# Supply.net
KiCad netlist of a schematic drawn in Altium Designer
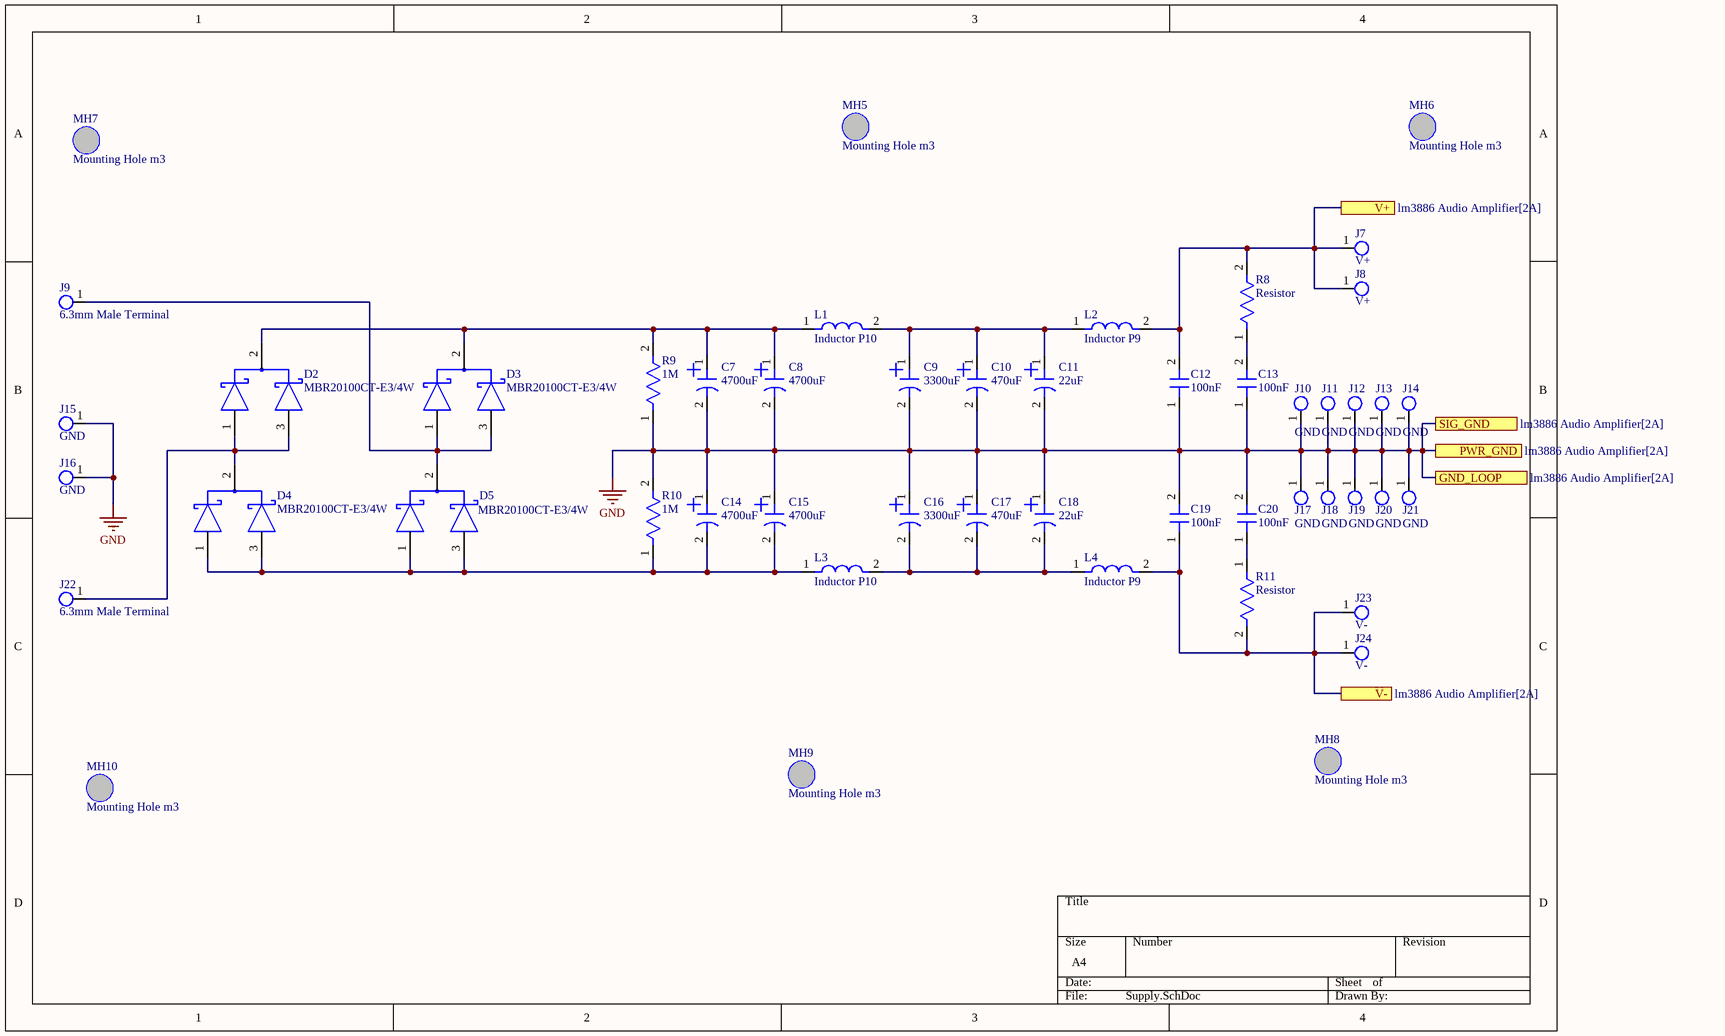
[diagram p0: Supply.SchDoc]

(export (version "E")
  (design (tool "Eeschema 10.0.6"))
  (components
    (comp (ref "C7")
      (value "4700uF")
      (footprint "Capacitor electrolytic 25x41mm")
      (libsource (lib "lm3886 Schlib") (part "Capacitor Polar"))
    )
    (comp (ref "C8")
      (value "4700uF")
      (footprint "Capacitor electrolytic 25x41mm")
      (libsource (lib "lm3886 Schlib") (part "Capacitor Polar"))
    )
    (comp (ref "C9")
      (value "3300uF")
      (footprint "Capacitor electrolytic 16x21mm")
      (libsource (lib "lm3886 Schlib") (part "Capacitor Polar"))
    )
    (comp (ref "C10")
      (value "470uF")
      (footprint "Capacitor electrolytic 10x16mm")
      (libsource (lib "lm3886 Schlib") (part "Capacitor Polar"))
    )
    (comp (ref "C11")
      (value "22uF")
      (footprint "Capacitor electrolytic 5x11mm")
      (libsource (lib "lm3886 Schlib") (part "Capacitor Polar"))
    )
    (comp (ref "C12")
      (value "100nF")
      (footprint "Capacitor P5 3x7.5mm")
      (libsource (lib "lm3886 Schlib") (part "Capacitor"))
    )
    (comp (ref "C13")
      (value "100nF")
      (footprint "Capacitor P5 5x7.5mm")
      (libsource (lib "lm3886 Schlib") (part "Capacitor"))
    )
    (comp (ref "C14")
      (value "4700uF")
      (footprint "Capacitor electrolytic 25x41mm")
      (libsource (lib "lm3886 Schlib") (part "Capacitor Polar"))
    )
    (comp (ref "C15")
      (value "4700uF")
      (footprint "Capacitor electrolytic 25x41mm")
      (libsource (lib "lm3886 Schlib") (part "Capacitor Polar"))
    )
    (comp (ref "C16")
      (value "3300uF")
      (footprint "Capacitor electrolytic 16x21mm")
      (libsource (lib "lm3886 Schlib") (part "Capacitor Polar"))
    )
    (comp (ref "C17")
      (value "470uF")
      (footprint "Capacitor electrolytic 10x16mm")
      (libsource (lib "lm3886 Schlib") (part "Capacitor Polar"))
    )
    (comp (ref "C18")
      (value "22uF")
      (footprint "Capacitor electrolytic 5x11mm")
      (libsource (lib "lm3886 Schlib") (part "Capacitor Polar"))
    )
    (comp (ref "C19")
      (value "100nF")
      (footprint "Capacitor P5 3x7.5mm")
      (libsource (lib "lm3886 Schlib") (part "Capacitor"))
    )
    (comp (ref "C20")
      (value "100nF")
      (footprint "Capacitor P5 5x7.5mm")
      (libsource (lib "lm3886 Schlib") (part "Capacitor"))
    )
    (comp (ref "D2")
      (value "MBR20100CT-E3/4W")
      (footprint "FP-MBR20100CT-E3-4W-MFG")
      (description "MBR20100CT-E3/4W Dual Common-Cathode High-Voltage Schottky Rectifier")
      (libsource (lib "Altium Content Vault") (part "213139fa27cf652ab25f6c90a0a0ee5"))
    )
    (comp (ref "D3")
      (value "MBR20100CT-E3/4W")
      (footprint "FP-MBR20100CT-E3-4W-MFG")
      (description "MBR20100CT-E3/4W Dual Common-Cathode High-Voltage Schottky Rectifier")
      (libsource (lib "Altium Content Vault") (part "213139fa27cf652ab25f6c90a0a0ee5"))
    )
    (comp (ref "D4")
      (value "MBR20100CT-E3/4W")
      (footprint "FP-MBR20100CT-E3-4W-MFG")
      (description "MBR20100CT-E3/4W Dual Common-Cathode High-Voltage Schottky Rectifier")
      (libsource (lib "Altium Content Vault") (part "213139fa27cf652ab25f6c90a0a0ee5"))
    )
    (comp (ref "D5")
      (value "MBR20100CT-E3/4W")
      (footprint "FP-MBR20100CT-E3-4W-MFG")
      (description "MBR20100CT-E3/4W Dual Common-Cathode High-Voltage Schottky Rectifier")
      (libsource (lib "Altium Content Vault") (part "213139fa27cf652ab25f6c90a0a0ee5"))
    )
    (comp (ref "J7")
      (value "V+")
      (footprint "Terminal 6.3mm male")
      (libsource (lib "lm3886 Schlib") (part "6.3mm Male Terminal"))
    )
    (comp (ref "J8")
      (value "V+")
      (footprint "Terminal 6.3mm male")
      (libsource (lib "lm3886 Schlib") (part "6.3mm Male Terminal"))
    )
    (comp (ref "J9")
      (value "6.3mm Male Terminal")
      (footprint "Terminal 6.3mm male")
      (libsource (lib "lm3886 Schlib") (part "6.3mm Male Terminal"))
    )
    (comp (ref "J10")
      (value "GND")
      (footprint "Terminal 6.3mm male")
      (libsource (lib "lm3886 Schlib") (part "6.3mm Male Terminal"))
    )
    (comp (ref "J11")
      (value "GND")
      (footprint "Terminal 6.3mm male")
      (libsource (lib "lm3886 Schlib") (part "6.3mm Male Terminal"))
    )
    (comp (ref "J12")
      (value "GND")
      (footprint "Terminal 6.3mm male")
      (libsource (lib "lm3886 Schlib") (part "6.3mm Male Terminal"))
    )
    (comp (ref "J13")
      (value "GND")
      (footprint "Terminal 6.3mm male")
      (libsource (lib "lm3886 Schlib") (part "6.3mm Male Terminal"))
    )
    (comp (ref "J14")
      (value "GND")
      (footprint "Terminal 6.3mm male")
      (libsource (lib "lm3886 Schlib") (part "6.3mm Male Terminal"))
    )
    (comp (ref "J15")
      (value "GND")
      (footprint "Terminal 6.3mm male")
      (libsource (lib "lm3886 Schlib") (part "6.3mm Male Terminal"))
    )
    (comp (ref "J16")
      (value "GND")
      (footprint "Terminal 6.3mm male")
      (libsource (lib "lm3886 Schlib") (part "6.3mm Male Terminal"))
    )
    (comp (ref "J17")
      (value "GND")
      (footprint "Terminal 6.3mm male")
      (libsource (lib "lm3886 Schlib") (part "6.3mm Male Terminal"))
    )
    (comp (ref "J18")
      (value "GND")
      (footprint "Terminal 6.3mm male")
      (libsource (lib "lm3886 Schlib") (part "6.3mm Male Terminal"))
    )
    (comp (ref "J19")
      (value "GND")
      (footprint "Terminal 6.3mm male")
      (libsource (lib "lm3886 Schlib") (part "6.3mm Male Terminal"))
    )
    (comp (ref "J20")
      (value "GND")
      (footprint "Terminal 6.3mm male")
      (libsource (lib "lm3886 Schlib") (part "6.3mm Male Terminal"))
    )
    (comp (ref "J21")
      (value "GND")
      (footprint "Terminal 6.3mm male")
      (libsource (lib "lm3886 Schlib") (part "6.3mm Male Terminal"))
    )
    (comp (ref "J22")
      (value "6.3mm Male Terminal")
      (footprint "Terminal 6.3mm male")
      (libsource (lib "lm3886 Schlib") (part "6.3mm Male Terminal"))
    )
    (comp (ref "J23")
      (value "V-")
      (footprint "Terminal 6.3mm male")
      (libsource (lib "lm3886 Schlib") (part "6.3mm Male Terminal"))
    )
    (comp (ref "J24")
      (value "V-")
      (footprint "Terminal 6.3mm male")
      (libsource (lib "lm3886 Schlib") (part "6.3mm Male Terminal"))
    )
    (comp (ref "L1")
      (value "Inductor P10")
      (footprint "Inductor p10")
      (libsource (lib "lm3886 Schlib") (part "Inductor"))
    )
    (comp (ref "L2")
      (value "Inductor P9")
      (footprint "Inductor p10")
      (libsource (lib "lm3886 Schlib") (part "Inductor"))
    )
    (comp (ref "L3")
      (value "Inductor P10")
      (footprint "Inductor p10")
      (libsource (lib "lm3886 Schlib") (part "Inductor"))
    )
    (comp (ref "L4")
      (value "Inductor P9")
      (footprint "Inductor p10")
      (libsource (lib "lm3886 Schlib") (part "Inductor"))
    )
    (comp (ref "MH5")
      (value "Mounting Hole m3")
      (footprint "Mounting Hole")
      (libsource (lib "lm3886 Schlib") (part "Mounting Hole m3"))
    )
    (comp (ref "MH6")
      (value "Mounting Hole m3")
      (footprint "Mounting Hole")
      (libsource (lib "lm3886 Schlib") (part "Mounting Hole m3"))
    )
    (comp (ref "MH7")
      (value "Mounting Hole m3")
      (footprint "Mounting Hole")
      (libsource (lib "lm3886 Schlib") (part "Mounting Hole m3"))
    )
    (comp (ref "MH8")
      (value "Mounting Hole m3")
      (footprint "Mounting Hole")
      (libsource (lib "lm3886 Schlib") (part "Mounting Hole m3"))
    )
    (comp (ref "MH9")
      (value "Mounting Hole m3")
      (footprint "Mounting Hole")
      (libsource (lib "lm3886 Schlib") (part "Mounting Hole m3"))
    )
    (comp (ref "MH10")
      (value "Mounting Hole m3")
      (footprint "Mounting Hole")
      (libsource (lib "lm3886 Schlib") (part "Mounting Hole m3"))
    )
    (comp (ref "R8")
      (value "Resistor")
      (footprint "Resistor 0617 2W Vertical")
      (libsource (lib "lm3886 Schlib") (part "Resistor"))
    )
    (comp (ref "R9")
      (value "1M")
      (footprint "Resistor 0207 1/4W")
      (libsource (lib "lm3886 Schlib") (part "Resistor"))
    )
    (comp (ref "R10")
      (value "1M")
      (footprint "Resistor 0207 1/4W")
      (libsource (lib "lm3886 Schlib") (part "Resistor"))
    )
    (comp (ref "R11")
      (value "Resistor")
      (footprint "Resistor 0617 2W Vertical")
      (libsource (lib "lm3886 Schlib") (part "Resistor"))
    )
  )
  (nets
    (net (code "1") (name "/V+") (class "Default")
      (node (ref "C12") (pin "2") (pintype "passive"))
      (node (ref "J7") (pin "1") (pintype "passive"))
      (node (ref "J8") (pin "1") (pintype "passive"))
      (node (ref "L2") (pin "2") (pintype "passive"))
      (node (ref "R8") (pin "2") (pintype "passive"))
    )
    (net (code "2") (name "/V-") (class "Default")
      (node (ref "C19") (pin "1") (pintype "passive"))
      (node (ref "J23") (pin "1") (pintype "passive"))
      (node (ref "J24") (pin "1") (pintype "passive"))
      (node (ref "L4") (pin "2") (pintype "passive"))
      (node (ref "R11") (pin "2") (pintype "passive"))
    )
    (net (code "3") (name "GND") (class "Default")
      (node (ref "C10") (pin "2") (pintype "passive"))
      (node (ref "C11") (pin "2") (pintype "passive"))
      (node (ref "C12") (pin "1") (pintype "passive"))
      (node (ref "C13") (pin "1") (pintype "passive"))
      (node (ref "C14") (pin "1") (pintype "passive"))
      (node (ref "C15") (pin "1") (pintype "passive"))
      (node (ref "C16") (pin "1") (pintype "passive"))
      (node (ref "C17") (pin "1") (pintype "passive"))
      (node (ref "C18") (pin "1") (pintype "passive"))
      (node (ref "C19") (pin "2") (pintype "passive"))
      (node (ref "C20") (pin "2") (pintype "passive"))
      (node (ref "C7") (pin "2") (pintype "passive"))
      (node (ref "C8") (pin "2") (pintype "passive"))
      (node (ref "C9") (pin "2") (pintype "passive"))
      (node (ref "J10") (pin "1") (pintype "passive"))
      (node (ref "J11") (pin "1") (pintype "passive"))
      (node (ref "J12") (pin "1") (pintype "passive"))
      (node (ref "J13") (pin "1") (pintype "passive"))
      (node (ref "J14") (pin "1") (pintype "passive"))
      (node (ref "J15") (pin "1") (pintype "passive"))
      (node (ref "J16") (pin "1") (pintype "passive"))
      (node (ref "J17") (pin "1") (pintype "passive"))
      (node (ref "J18") (pin "1") (pintype "passive"))
      (node (ref "J19") (pin "1") (pintype "passive"))
      (node (ref "J20") (pin "1") (pintype "passive"))
      (node (ref "J21") (pin "1") (pintype "passive"))
      (node (ref "R10") (pin "2") (pintype "passive"))
      (node (ref "R9") (pin "1") (pintype "passive"))
    )
    (net (code "4") (name "Net-(C10-Pad1)") (class "Default")
      (node (ref "C10") (pin "1") (pintype "passive"))
      (node (ref "C11") (pin "1") (pintype "passive"))
      (node (ref "C9") (pin "1") (pintype "passive"))
      (node (ref "L1") (pin "2") (pintype "passive"))
      (node (ref "L2") (pin "1") (pintype "passive"))
    )
    (net (code "5") (name "Net-(C13-Pad2)") (class "Default")
      (node (ref "C13") (pin "2") (pintype "passive"))
      (node (ref "R8") (pin "1") (pintype "passive"))
    )
    (net (code "6") (name "Net-(C16-Pad2)") (class "Default")
      (node (ref "C16") (pin "2") (pintype "passive"))
      (node (ref "C17") (pin "2") (pintype "passive"))
      (node (ref "C18") (pin "2") (pintype "passive"))
      (node (ref "L3") (pin "2") (pintype "passive"))
      (node (ref "L4") (pin "1") (pintype "passive"))
    )
    (net (code "7") (name "Net-(C20-Pad1)") (class "Default")
      (node (ref "C20") (pin "1") (pintype "passive"))
      (node (ref "R11") (pin "1") (pintype "passive"))
    )
    (net (code "8") (name "Net-(D2-1_ANODE)") (class "Default")
      (node (ref "D2") (pin "1") (pinfunction "1_ANODE_1") (pintype "passive"))
      (node (ref "D2") (pin "3") (pinfunction "2_ANODE_3") (pintype "passive"))
      (node (ref "D4") (pin "2") (pinfunction "COMMON_CATHODE_2") (pintype "passive"))
      (node (ref "J22") (pin "1") (pintype "passive"))
    )
    (net (code "9") (name "Net-(D2-COMMON_CATHODE)") (class "Default")
      (node (ref "C7") (pin "1") (pintype "passive"))
      (node (ref "C8") (pin "1") (pintype "passive"))
      (node (ref "D2") (pin "2") (pinfunction "COMMON_CATHODE_2") (pintype "passive"))
      (node (ref "D3") (pin "2") (pinfunction "COMMON_CATHODE_2") (pintype "passive"))
      (node (ref "L1") (pin "1") (pintype "passive"))
      (node (ref "R9") (pin "2") (pintype "passive"))
    )
    (net (code "10") (name "Net-(D3-1_ANODE)") (class "Default")
      (node (ref "D3") (pin "1") (pinfunction "1_ANODE_1") (pintype "passive"))
      (node (ref "D3") (pin "3") (pinfunction "2_ANODE_3") (pintype "passive"))
      (node (ref "D5") (pin "2") (pinfunction "COMMON_CATHODE_2") (pintype "passive"))
      (node (ref "J9") (pin "1") (pintype "passive"))
    )
    (net (code "11") (name "Net-(D4-1_ANODE)") (class "Default")
      (node (ref "C14") (pin "2") (pintype "passive"))
      (node (ref "C15") (pin "2") (pintype "passive"))
      (node (ref "D4") (pin "1") (pinfunction "1_ANODE_1") (pintype "passive"))
      (node (ref "D4") (pin "3") (pinfunction "2_ANODE_3") (pintype "passive"))
      (node (ref "D5") (pin "1") (pinfunction "1_ANODE_1") (pintype "passive"))
      (node (ref "D5") (pin "3") (pinfunction "2_ANODE_3") (pintype "passive"))
      (node (ref "L3") (pin "1") (pintype "passive"))
      (node (ref "R10") (pin "1") (pintype "passive"))
    )
  )
)
